# charger-test_2L.net
KiCad netlist of a schematic drawn in EAGLE
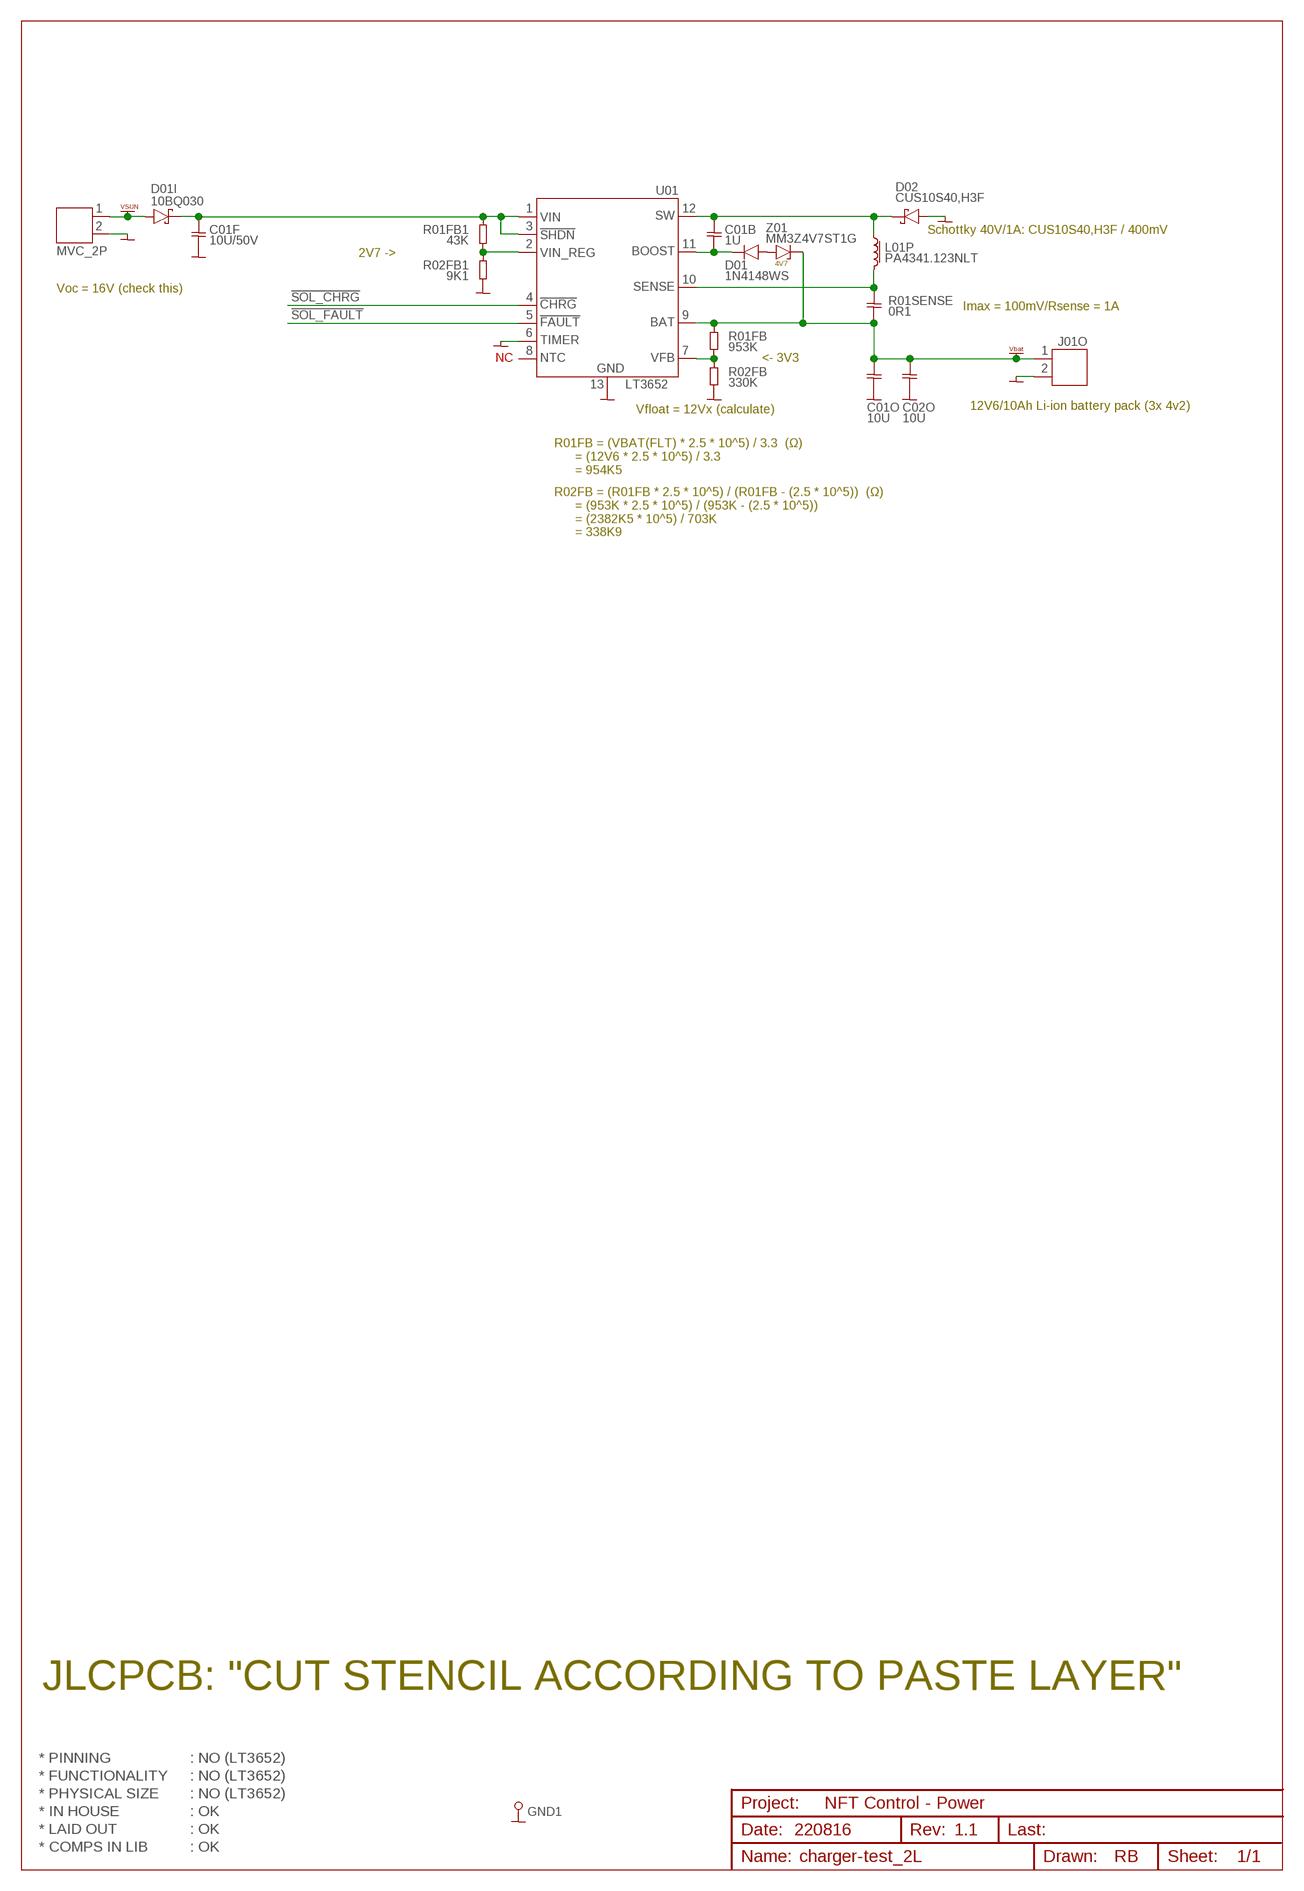
[diagram p0: schematic, sheet 1]

(export (version "E")
  (design (tool "Eeschema 10.0.6"))
  (components
    (comp (ref "C01B")
      (value "1U")
      (footprint "eagle-import:CAP0402")
      (libsource (lib "eagle-import") (part "CAP0402"))
    )
    (comp (ref "C01F")
      (value "10U/50V")
      (footprint "eagle-import:CAP0805")
      (libsource (lib "eagle-import") (part "CAP0805"))
    )
    (comp (ref "C01O")
      (value "10U")
      (footprint "eagle-import:CAP0805")
      (libsource (lib "eagle-import") (part "CAP0805"))
    )
    (comp (ref "C02O")
      (value "10U")
      (footprint "eagle-import:CAP0805")
      (libsource (lib "eagle-import") (part "CAP0805"))
    )
    (comp (ref "D01")
      (value "1N4148WS")
      (footprint "eagle-import:DIODE_SOD323")
      (libsource (lib "eagle-import") (part "DIODE_1N4148WS"))
    )
    (comp (ref "D01I")
      (value "10BQ030")
      (footprint "eagle-import:DIODE_SMB")
      (libsource (lib "eagle-import") (part "DIODE_10BQ030"))
    )
    (comp (ref "D02")
      (value "CUS10S40,H3F")
      (footprint "eagle-import:DIODE_SOD323")
      (libsource (lib "eagle-import") (part "DIODE_SCHOTTKY_SOD323"))
    )
    (comp (ref "GND1")
      (value "PIN_TEST")
      (footprint "eagle-import:HOLE_PTH_0.8MM")
      (libsource (lib "eagle-import") (part "PIN_TEST"))
    )
    (comp (ref "J01I")
      (value "MVC_2P")
      (footprint "eagle-import:CON_PHOENIX_COMBICON_MCV_HEADER_P")
      (libsource (lib "eagle-import") (part "CON_PHOENIX_COMBICON_MCV_HEADER_2P"))
    )
    (comp (ref "J01O")
      (value "CON_PHOENIX_COMBICON_MCV_HEADER_2P")
      (footprint "eagle-import:CON_PHOENIX_COMBICON_MCV_HEADER_P")
      (libsource (lib "eagle-import") (part "CON_PHOENIX_COMBICON_MCV_HEADER_2P"))
    )
    (comp (ref "L01P")
      (value "PA4341.123NLT")
      (footprint "eagle-import:L_PA4341")
      (libsource (lib "eagle-import") (part "L_PA4341"))
    )
    (comp (ref "R01FB")
      (value "953K")
      (footprint "eagle-import:RES0402")
      (libsource (lib "eagle-import") (part "RES0402"))
    )
    (comp (ref "R01FB1")
      (value "43K")
      (footprint "eagle-import:RES0603")
      (libsource (lib "eagle-import") (part "RES0603"))
    )
    (comp (ref "R01SENSE")
      (value "0R1")
      (footprint "eagle-import:CAP0603")
      (libsource (lib "eagle-import") (part "CAP0603"))
    )
    (comp (ref "R02FB")
      (value "330K")
      (footprint "eagle-import:RES0402")
      (libsource (lib "eagle-import") (part "RES0402"))
    )
    (comp (ref "R02FB1")
      (value "9K1")
      (footprint "eagle-import:RES0603")
      (libsource (lib "eagle-import") (part "RES0603"))
    )
    (comp (ref "U01")
      (value "LT3652")
      (footprint "eagle-import:MSOP-12_GND")
      (libsource (lib "eagle-import") (part "LT3652"))
    )
    (comp (ref "Z01")
      (value "MM3Z4V7ST1G")
      (footprint "eagle-import:ZENER_SOD323")
      (libsource (lib "eagle-import") (part "ZENER_SOD323"))
    )
  )
  (nets
    (net (code "1") (name "/~{SOL_CHRG}") (class "Default")
      (node (ref "U01") (pin "4") (pinfunction "4.~{CHRG}_4") (pintype "bidirectional"))
    )
    (net (code "2") (name "/~{SOL_FAULT}") (class "Default")
      (node (ref "U01") (pin "5") (pinfunction "5.~{FAULT}_5") (pintype "bidirectional"))
    )
    (net (code "3") (name "GND") (class "Default")
      (node (ref "C01F") (pin "2") (pinfunction "2_2") (pintype "passive"))
      (node (ref "C01O") (pin "2") (pinfunction "2_2") (pintype "passive"))
      (node (ref "C02O") (pin "2") (pinfunction "2_2") (pintype "passive"))
      (node (ref "D02") (pin "A") (pinfunction "A_A") (pintype "passive"))
      (node (ref "GND1") (pin "1") (pinfunction "P$1_1") (pintype "passive"))
      (node (ref "J01I") (pin "2") (pinfunction "2_2") (pintype "passive"))
      (node (ref "J01O") (pin "2") (pinfunction "2_2") (pintype "passive"))
      (node (ref "R02FB") (pin "1") (pinfunction "1_1") (pintype "passive"))
      (node (ref "R02FB1") (pin "1") (pinfunction "1_1") (pintype "passive"))
      (node (ref "U01") (pin "13") (pinfunction "GND_PAD_13") (pintype "bidirectional"))
      (node (ref "U01") (pin "6") (pinfunction "6.TIMER_6") (pintype "bidirectional"))
    )
    (net (code "4") (name "Net-(D01-+)") (class "Default")
      (node (ref "D01") (pin "A") (pinfunction "+_A") (pintype "passive"))
      (node (ref "Z01") (pin "A") (pinfunction "A_A") (pintype "passive"))
    )
    (net (code "5") (name "Net-(D01--)") (class "Default")
      (node (ref "C01B") (pin "2") (pinfunction "2_2") (pintype "passive"))
      (node (ref "D01") (pin "C") (pinfunction "-_C") (pintype "passive"))
      (node (ref "U01") (pin "11") (pinfunction "11.BOOST_11") (pintype "bidirectional"))
    )
    (net (code "6") (name "Net-(D01I--)") (class "Default")
      (node (ref "C01F") (pin "1") (pinfunction "1_1") (pintype "passive"))
      (node (ref "D01I") (pin "C") (pinfunction "-_C") (pintype "passive"))
      (node (ref "R01FB1") (pin "2") (pinfunction "2_2") (pintype "passive"))
      (node (ref "U01") (pin "1") (pinfunction "1.VIN_1") (pintype "bidirectional"))
      (node (ref "U01") (pin "3") (pinfunction "3.~{SHDN}_3") (pintype "bidirectional"))
    )
    (net (code "7") (name "Net-(L01P-1)") (class "Default")
      (node (ref "C01B") (pin "1") (pinfunction "1_1") (pintype "passive"))
      (node (ref "D02") (pin "C") (pinfunction "C_C") (pintype "passive"))
      (node (ref "L01P") (pin "P$1") (pinfunction "1_P$1") (pintype "passive"))
      (node (ref "U01") (pin "12") (pinfunction "12.SW_12") (pintype "bidirectional"))
    )
    (net (code "8") (name "Net-(L01P-2)") (class "Default")
      (node (ref "L01P") (pin "P$2") (pinfunction "2_P$2") (pintype "passive"))
      (node (ref "R01SENSE") (pin "2") (pinfunction "2_2") (pintype "passive"))
      (node (ref "U01") (pin "10") (pinfunction "10.SENSE_10") (pintype "bidirectional"))
    )
    (net (code "9") (name "Net-(U01-2.VIN_REG)") (class "Default")
      (node (ref "R01FB1") (pin "1") (pinfunction "1_1") (pintype "passive"))
      (node (ref "R02FB1") (pin "2") (pinfunction "2_2") (pintype "passive"))
      (node (ref "U01") (pin "2") (pinfunction "2.VIN_REG_2") (pintype "bidirectional"))
    )
    (net (code "10") (name "Net-(U01-7.VFB)") (class "Default")
      (node (ref "R01FB") (pin "1") (pinfunction "1_1") (pintype "passive"))
      (node (ref "R02FB") (pin "2") (pinfunction "2_2") (pintype "passive"))
      (node (ref "U01") (pin "7") (pinfunction "7.VFB_7") (pintype "bidirectional"))
    )
    (net (code "11") (name "VBAT") (class "Default")
      (node (ref "C01O") (pin "1") (pinfunction "1_1") (pintype "passive"))
      (node (ref "C02O") (pin "1") (pinfunction "1_1") (pintype "passive"))
      (node (ref "J01O") (pin "1") (pinfunction "1_1") (pintype "passive"))
      (node (ref "R01FB") (pin "2") (pinfunction "2_2") (pintype "passive"))
      (node (ref "R01SENSE") (pin "1") (pinfunction "1_1") (pintype "passive"))
      (node (ref "U01") (pin "9") (pinfunction "9.BAT_9") (pintype "bidirectional"))
      (node (ref "Z01") (pin "C") (pinfunction "C_C") (pintype "passive"))
    )
    (net (code "12") (name "VSUN") (class "Default")
      (node (ref "D01I") (pin "A") (pinfunction "+_A") (pintype "passive"))
      (node (ref "J01I") (pin "1") (pinfunction "1_1") (pintype "passive"))
    )
    (net (code "13") (name "unconnected-(U01-8.NTC-Pad8)") (class "Default")
      (node (ref "U01") (pin "8") (pinfunction "8.NTC_8") (pintype "bidirectional"))
    )
  )
)
